# 8CH_Dimmer.net
KiCad netlist of a schematic drawn in EAGLE
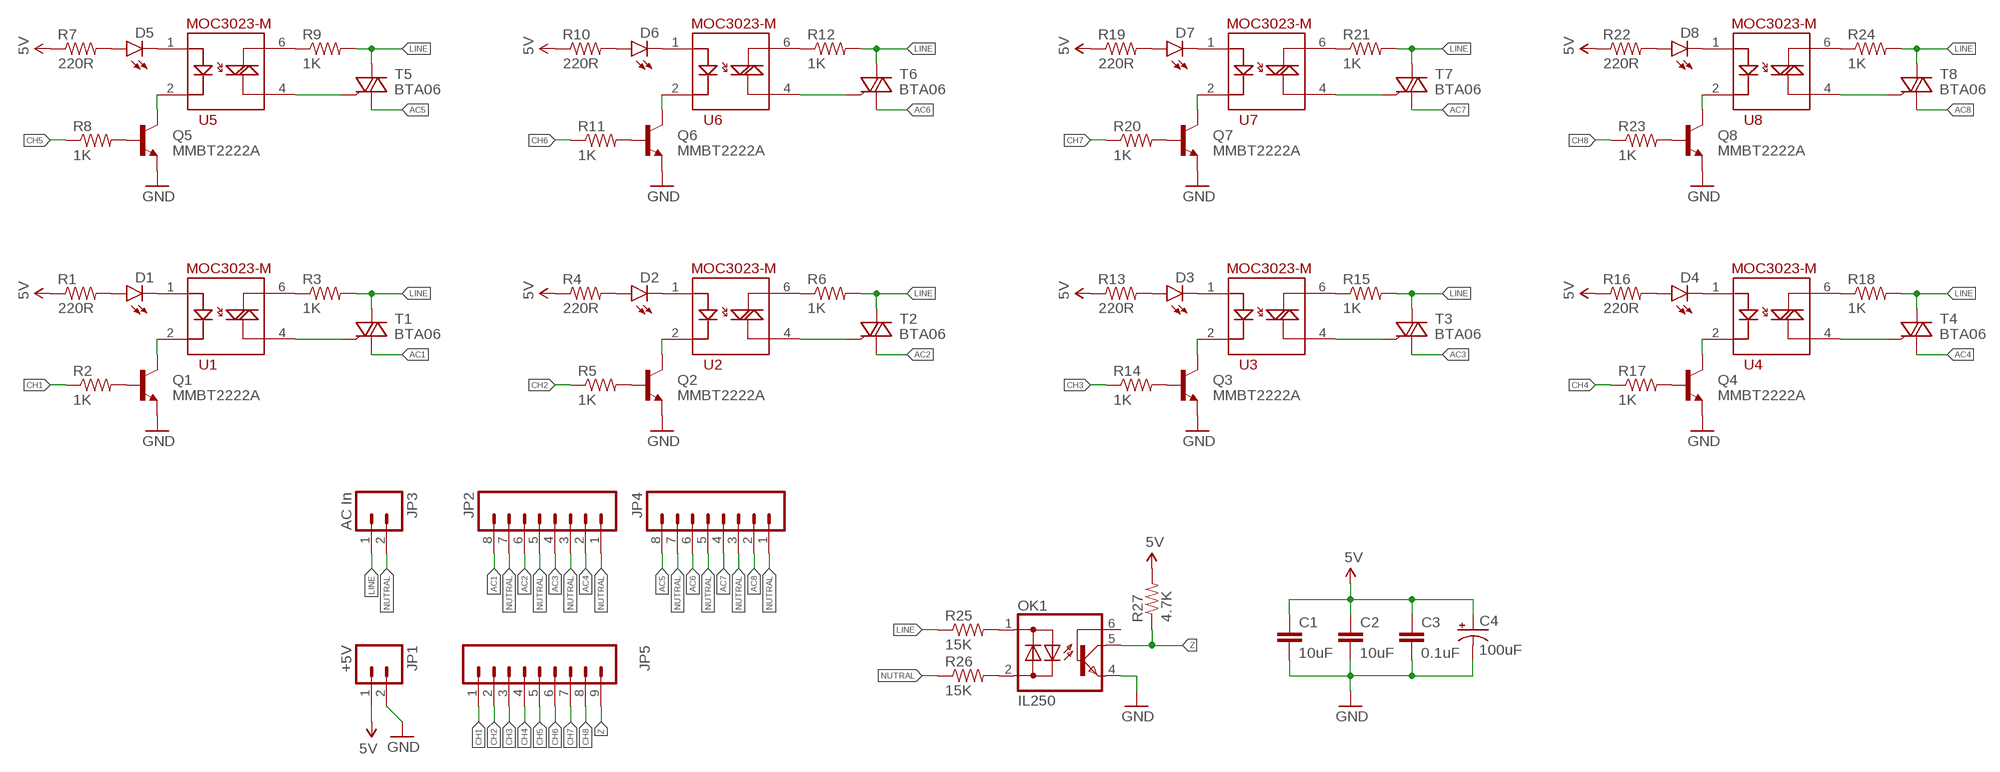
[diagram p0: schematic, sheet 1]

(export (version "E")
  (design (tool "Eeschema 10.0.6"))
  (components
    (comp (ref "C1")
      (value "10uF")
      (footprint "eagle-import:0805")
      (libsource (lib "eagle-import") (part "CAP0805"))
    )
    (comp (ref "C2")
      (value "10uF")
      (footprint "eagle-import:0805")
      (libsource (lib "eagle-import") (part "CAP0805"))
    )
    (comp (ref "C3")
      (value "0.1uF")
      (footprint "eagle-import:0805")
      (libsource (lib "eagle-import") (part "CAP0805"))
    )
    (comp (ref "C4")
      (value "100uF")
      (footprint "eagle-import:E2,5-5")
      (libsource (lib "eagle-import") (part "CPOL-USE2.5-5"))
    )
    (comp (ref "D1")
      (value "LED3MM")
      (footprint "eagle-import:LED3MM")
      (libsource (lib "eagle-import") (part "LED3MM"))
    )
    (comp (ref "D2")
      (value "LED3MM")
      (footprint "eagle-import:LED3MM")
      (libsource (lib "eagle-import") (part "LED3MM"))
    )
    (comp (ref "D3")
      (value "LED3MM")
      (footprint "eagle-import:LED3MM")
      (libsource (lib "eagle-import") (part "LED3MM"))
    )
    (comp (ref "D4")
      (value "LED3MM")
      (footprint "eagle-import:LED3MM")
      (libsource (lib "eagle-import") (part "LED3MM"))
    )
    (comp (ref "D5")
      (value "LED3MM")
      (footprint "eagle-import:LED3MM")
      (libsource (lib "eagle-import") (part "LED3MM"))
    )
    (comp (ref "D6")
      (value "LED3MM")
      (footprint "eagle-import:LED3MM")
      (libsource (lib "eagle-import") (part "LED3MM"))
    )
    (comp (ref "D7")
      (value "LED3MM")
      (footprint "eagle-import:LED3MM")
      (libsource (lib "eagle-import") (part "LED3MM"))
    )
    (comp (ref "D8")
      (value "LED3MM")
      (footprint "eagle-import:LED3MM")
      (libsource (lib "eagle-import") (part "LED3MM"))
    )
    (comp (ref "JP1")
      (value "+5V")
      (footprint "eagle-import:SCREWTERMINAL-3.5MM-2")
      (libsource (lib "eagle-import") (part "M023.5MM"))
    )
    (comp (ref "JP2")
      (value "M083.5MM-8")
      (footprint "eagle-import:SCREWTERMINAL-3.5MM-8")
      (libsource (lib "eagle-import") (part "M083.5MM-8"))
    )
    (comp (ref "JP3")
      (value "AC In")
      (footprint "eagle-import:SCREWTERMINAL-3.5MM-2")
      (libsource (lib "eagle-import") (part "M023.5MM"))
    )
    (comp (ref "JP4")
      (value "M083.5MM-8")
      (footprint "eagle-import:SCREWTERMINAL-3.5MM-8")
      (libsource (lib "eagle-import") (part "M083.5MM-8"))
    )
    (comp (ref "JP5")
      (value "M09")
      (footprint "eagle-import:1X09")
      (libsource (lib "eagle-import") (part "M09"))
    )
    (comp (ref "OK1")
      (value "IL250")
      (footprint "eagle-import:DIL06")
      (fields (field (name "MF") "VISHAY/TELEFUNKEN"))
      (libsource (lib "eagle-import") (part "IL250"))
    )
    (comp (ref "Q1")
      (value "MMBT2222A")
      (footprint "eagle-import:SOT23-3")
      (libsource (lib "eagle-import") (part "TRANSISTOR_NPNMMBT2222A"))
    )
    (comp (ref "Q2")
      (value "MMBT2222A")
      (footprint "eagle-import:SOT23-3")
      (libsource (lib "eagle-import") (part "TRANSISTOR_NPNMMBT2222A"))
    )
    (comp (ref "Q3")
      (value "MMBT2222A")
      (footprint "eagle-import:SOT23-3")
      (libsource (lib "eagle-import") (part "TRANSISTOR_NPNMMBT2222A"))
    )
    (comp (ref "Q4")
      (value "MMBT2222A")
      (footprint "eagle-import:SOT23-3")
      (libsource (lib "eagle-import") (part "TRANSISTOR_NPNMMBT2222A"))
    )
    (comp (ref "Q5")
      (value "MMBT2222A")
      (footprint "eagle-import:SOT23-3")
      (libsource (lib "eagle-import") (part "TRANSISTOR_NPNMMBT2222A"))
    )
    (comp (ref "Q6")
      (value "MMBT2222A")
      (footprint "eagle-import:SOT23-3")
      (libsource (lib "eagle-import") (part "TRANSISTOR_NPNMMBT2222A"))
    )
    (comp (ref "Q7")
      (value "MMBT2222A")
      (footprint "eagle-import:SOT23-3")
      (libsource (lib "eagle-import") (part "TRANSISTOR_NPNMMBT2222A"))
    )
    (comp (ref "Q8")
      (value "MMBT2222A")
      (footprint "eagle-import:SOT23-3")
      (libsource (lib "eagle-import") (part "TRANSISTOR_NPNMMBT2222A"))
    )
    (comp (ref "R1")
      (value "220R")
      (footprint "eagle-import:0805")
      (libsource (lib "eagle-import") (part "RESISTOR0805-RES"))
    )
    (comp (ref "R2")
      (value "1K")
      (footprint "eagle-import:0805")
      (libsource (lib "eagle-import") (part "RESISTOR0805-RES"))
    )
    (comp (ref "R3")
      (value "1K")
      (footprint "eagle-import:AXIAL-0.5")
      (libsource (lib "eagle-import") (part "RESISTORPTH-1/2W"))
    )
    (comp (ref "R4")
      (value "220R")
      (footprint "eagle-import:0805")
      (libsource (lib "eagle-import") (part "RESISTOR0805-RES"))
    )
    (comp (ref "R5")
      (value "1K")
      (footprint "eagle-import:0805")
      (libsource (lib "eagle-import") (part "RESISTOR0805-RES"))
    )
    (comp (ref "R6")
      (value "1K")
      (footprint "eagle-import:AXIAL-0.5")
      (libsource (lib "eagle-import") (part "RESISTORPTH-1/2W"))
    )
    (comp (ref "R7")
      (value "220R")
      (footprint "eagle-import:0805")
      (libsource (lib "eagle-import") (part "RESISTOR0805-RES"))
    )
    (comp (ref "R8")
      (value "1K")
      (footprint "eagle-import:0805")
      (libsource (lib "eagle-import") (part "RESISTOR0805-RES"))
    )
    (comp (ref "R9")
      (value "1K")
      (footprint "eagle-import:AXIAL-0.5")
      (libsource (lib "eagle-import") (part "RESISTORPTH-1/2W"))
    )
    (comp (ref "R10")
      (value "220R")
      (footprint "eagle-import:0805")
      (libsource (lib "eagle-import") (part "RESISTOR0805-RES"))
    )
    (comp (ref "R11")
      (value "1K")
      (footprint "eagle-import:0805")
      (libsource (lib "eagle-import") (part "RESISTOR0805-RES"))
    )
    (comp (ref "R12")
      (value "1K")
      (footprint "eagle-import:AXIAL-0.5")
      (libsource (lib "eagle-import") (part "RESISTORPTH-1/2W"))
    )
    (comp (ref "R13")
      (value "220R")
      (footprint "eagle-import:0805")
      (libsource (lib "eagle-import") (part "RESISTOR0805-RES"))
    )
    (comp (ref "R14")
      (value "1K")
      (footprint "eagle-import:0805")
      (libsource (lib "eagle-import") (part "RESISTOR0805-RES"))
    )
    (comp (ref "R15")
      (value "1K")
      (footprint "eagle-import:AXIAL-0.5")
      (libsource (lib "eagle-import") (part "RESISTORPTH-1/2W"))
    )
    (comp (ref "R16")
      (value "220R")
      (footprint "eagle-import:0805")
      (libsource (lib "eagle-import") (part "RESISTOR0805-RES"))
    )
    (comp (ref "R17")
      (value "1K")
      (footprint "eagle-import:0805")
      (libsource (lib "eagle-import") (part "RESISTOR0805-RES"))
    )
    (comp (ref "R18")
      (value "1K")
      (footprint "eagle-import:AXIAL-0.5")
      (libsource (lib "eagle-import") (part "RESISTORPTH-1/2W"))
    )
    (comp (ref "R19")
      (value "220R")
      (footprint "eagle-import:0805")
      (libsource (lib "eagle-import") (part "RESISTOR0805-RES"))
    )
    (comp (ref "R20")
      (value "1K")
      (footprint "eagle-import:0805")
      (libsource (lib "eagle-import") (part "RESISTOR0805-RES"))
    )
    (comp (ref "R21")
      (value "1K")
      (footprint "eagle-import:AXIAL-0.5")
      (libsource (lib "eagle-import") (part "RESISTORPTH-1/2W"))
    )
    (comp (ref "R22")
      (value "220R")
      (footprint "eagle-import:0805")
      (libsource (lib "eagle-import") (part "RESISTOR0805-RES"))
    )
    (comp (ref "R23")
      (value "1K")
      (footprint "eagle-import:0805")
      (libsource (lib "eagle-import") (part "RESISTOR0805-RES"))
    )
    (comp (ref "R24")
      (value "1K")
      (footprint "eagle-import:AXIAL-0.5")
      (libsource (lib "eagle-import") (part "RESISTORPTH-1/2W"))
    )
    (comp (ref "R25")
      (value "15K")
      (footprint "eagle-import:AXIAL-0.5")
      (libsource (lib "eagle-import") (part "RESISTORPTH-1/2W"))
    )
    (comp (ref "R26")
      (value "15K")
      (footprint "eagle-import:AXIAL-0.5")
      (libsource (lib "eagle-import") (part "RESISTORPTH-1/2W"))
    )
    (comp (ref "R27")
      (value "4.7K")
      (footprint "eagle-import:0805")
      (libsource (lib "eagle-import") (part "RESISTOR0805-RES"))
    )
    (comp (ref "T1")
      (value "BTA06")
      (footprint "eagle-import:TO220-V")
      (libsource (lib "eagle-import") (part "BTA06"))
    )
    (comp (ref "T2")
      (value "BTA06")
      (footprint "eagle-import:TO220-V")
      (libsource (lib "eagle-import") (part "BTA06"))
    )
    (comp (ref "T3")
      (value "BTA06")
      (footprint "eagle-import:TO220-V")
      (libsource (lib "eagle-import") (part "BTA06"))
    )
    (comp (ref "T4")
      (value "BTA06")
      (footprint "eagle-import:TO220-V")
      (libsource (lib "eagle-import") (part "BTA06"))
    )
    (comp (ref "T5")
      (value "BTA06")
      (footprint "eagle-import:TO220-V")
      (libsource (lib "eagle-import") (part "BTA06"))
    )
    (comp (ref "T6")
      (value "BTA06")
      (footprint "eagle-import:TO220-V")
      (libsource (lib "eagle-import") (part "BTA06"))
    )
    (comp (ref "T7")
      (value "BTA06")
      (footprint "eagle-import:TO220-V")
      (libsource (lib "eagle-import") (part "BTA06"))
    )
    (comp (ref "T8")
      (value "BTA06")
      (footprint "eagle-import:TO220-V")
      (libsource (lib "eagle-import") (part "BTA06"))
    )
    (comp (ref "U1")
      (value "MOC3023-M")
      (footprint "eagle-import:DIL06")
      (libsource (lib "eagle-import") (part "MOC3031-M"))
    )
    (comp (ref "U2")
      (value "MOC3023-M")
      (footprint "eagle-import:DIL06")
      (libsource (lib "eagle-import") (part "MOC3031-M"))
    )
    (comp (ref "U3")
      (value "MOC3023-M")
      (footprint "eagle-import:DIL06")
      (libsource (lib "eagle-import") (part "MOC3031-M"))
    )
    (comp (ref "U4")
      (value "MOC3023-M")
      (footprint "eagle-import:DIL06")
      (libsource (lib "eagle-import") (part "MOC3031-M"))
    )
    (comp (ref "U5")
      (value "MOC3023-M")
      (footprint "eagle-import:DIL06")
      (libsource (lib "eagle-import") (part "MOC3031-M"))
    )
    (comp (ref "U6")
      (value "MOC3023-M")
      (footprint "eagle-import:DIL06")
      (libsource (lib "eagle-import") (part "MOC3031-M"))
    )
    (comp (ref "U7")
      (value "MOC3023-M")
      (footprint "eagle-import:DIL06")
      (libsource (lib "eagle-import") (part "MOC3031-M"))
    )
    (comp (ref "U8")
      (value "MOC3023-M")
      (footprint "eagle-import:DIL06")
      (libsource (lib "eagle-import") (part "MOC3031-M"))
    )
  )
  (nets
    (net (code "1") (name "5V") (class "Default")
      (node (ref "C1") (pin "1") (pinfunction "1_1") (pintype "passive"))
      (node (ref "C2") (pin "1") (pinfunction "1_1") (pintype "passive"))
      (node (ref "C3") (pin "1") (pinfunction "1_1") (pintype "passive"))
      (node (ref "C4") (pin "+") (pinfunction "+_+") (pintype "passive"))
      (node (ref "JP1") (pin "1") (pinfunction "1_1") (pintype "passive"))
      (node (ref "R1") (pin "1") (pinfunction "1_1") (pintype "passive"))
      (node (ref "R10") (pin "1") (pinfunction "1_1") (pintype "passive"))
      (node (ref "R13") (pin "1") (pinfunction "1_1") (pintype "passive"))
      (node (ref "R16") (pin "1") (pinfunction "1_1") (pintype "passive"))
      (node (ref "R19") (pin "1") (pinfunction "1_1") (pintype "passive"))
      (node (ref "R22") (pin "1") (pinfunction "1_1") (pintype "passive"))
      (node (ref "R27") (pin "2") (pinfunction "2_2") (pintype "passive"))
      (node (ref "R4") (pin "1") (pinfunction "1_1") (pintype "passive"))
      (node (ref "R7") (pin "1") (pinfunction "1_1") (pintype "passive"))
    )
    (net (code "2") (name "AC1") (class "Default")
      (node (ref "JP2") (pin "8") (pinfunction "8_8") (pintype "passive"))
      (node (ref "T1") (pin "1") (pinfunction "A1_1") (pintype "passive"))
    )
    (net (code "3") (name "AC2") (class "Default")
      (node (ref "JP2") (pin "6") (pinfunction "6_6") (pintype "passive"))
      (node (ref "T2") (pin "1") (pinfunction "A1_1") (pintype "passive"))
    )
    (net (code "4") (name "AC3") (class "Default")
      (node (ref "JP2") (pin "4") (pinfunction "4_4") (pintype "passive"))
      (node (ref "T3") (pin "1") (pinfunction "A1_1") (pintype "passive"))
    )
    (net (code "5") (name "AC4") (class "Default")
      (node (ref "JP2") (pin "2") (pinfunction "2_2") (pintype "passive"))
      (node (ref "T4") (pin "1") (pinfunction "A1_1") (pintype "passive"))
    )
    (net (code "6") (name "AC5") (class "Default")
      (node (ref "JP4") (pin "8") (pinfunction "8_8") (pintype "passive"))
      (node (ref "T5") (pin "1") (pinfunction "A1_1") (pintype "passive"))
    )
    (net (code "7") (name "AC6") (class "Default")
      (node (ref "JP4") (pin "6") (pinfunction "6_6") (pintype "passive"))
      (node (ref "T6") (pin "1") (pinfunction "A1_1") (pintype "passive"))
    )
    (net (code "8") (name "AC7") (class "Default")
      (node (ref "JP4") (pin "4") (pinfunction "4_4") (pintype "passive"))
      (node (ref "T7") (pin "1") (pinfunction "A1_1") (pintype "passive"))
    )
    (net (code "9") (name "AC8") (class "Default")
      (node (ref "JP4") (pin "2") (pinfunction "2_2") (pintype "passive"))
      (node (ref "T8") (pin "1") (pinfunction "A1_1") (pintype "passive"))
    )
    (net (code "10") (name "CH1") (class "Default")
      (node (ref "JP5") (pin "1") (pinfunction "1_1") (pintype "passive"))
      (node (ref "R2") (pin "1") (pinfunction "1_1") (pintype "passive"))
    )
    (net (code "11") (name "CH2") (class "Default")
      (node (ref "JP5") (pin "2") (pinfunction "2_2") (pintype "passive"))
      (node (ref "R5") (pin "1") (pinfunction "1_1") (pintype "passive"))
    )
    (net (code "12") (name "CH3") (class "Default")
      (node (ref "JP5") (pin "3") (pinfunction "3_3") (pintype "passive"))
      (node (ref "R14") (pin "1") (pinfunction "1_1") (pintype "passive"))
    )
    (net (code "13") (name "CH4") (class "Default")
      (node (ref "JP5") (pin "4") (pinfunction "4_4") (pintype "passive"))
      (node (ref "R17") (pin "1") (pinfunction "1_1") (pintype "passive"))
    )
    (net (code "14") (name "CH5") (class "Default")
      (node (ref "JP5") (pin "5") (pinfunction "5_5") (pintype "passive"))
      (node (ref "R8") (pin "1") (pinfunction "1_1") (pintype "passive"))
    )
    (net (code "15") (name "CH6") (class "Default")
      (node (ref "JP5") (pin "6") (pinfunction "6_6") (pintype "passive"))
      (node (ref "R11") (pin "1") (pinfunction "1_1") (pintype "passive"))
    )
    (net (code "16") (name "CH7") (class "Default")
      (node (ref "JP5") (pin "7") (pinfunction "7_7") (pintype "passive"))
      (node (ref "R20") (pin "1") (pinfunction "1_1") (pintype "passive"))
    )
    (net (code "17") (name "CH8") (class "Default")
      (node (ref "JP5") (pin "8") (pinfunction "8_8") (pintype "passive"))
      (node (ref "R23") (pin "1") (pinfunction "1_1") (pintype "passive"))
    )
    (net (code "18") (name "GND") (class "Default")
      (node (ref "C1") (pin "2") (pinfunction "2_2") (pintype "passive"))
      (node (ref "C2") (pin "2") (pinfunction "2_2") (pintype "passive"))
      (node (ref "C3") (pin "2") (pinfunction "2_2") (pintype "passive"))
      (node (ref "C4") (pin "-") (pinfunction "-_-") (pintype "passive"))
      (node (ref "JP1") (pin "2") (pinfunction "2_2") (pintype "passive"))
      (node (ref "OK1") (pin "4") (pinfunction "E_4") (pintype "passive"))
      (node (ref "Q1") (pin "2") (pinfunction "E_2") (pintype "passive"))
      (node (ref "Q2") (pin "2") (pinfunction "E_2") (pintype "passive"))
      (node (ref "Q3") (pin "2") (pinfunction "E_2") (pintype "passive"))
      (node (ref "Q4") (pin "2") (pinfunction "E_2") (pintype "passive"))
      (node (ref "Q5") (pin "2") (pinfunction "E_2") (pintype "passive"))
      (node (ref "Q6") (pin "2") (pinfunction "E_2") (pintype "passive"))
      (node (ref "Q7") (pin "2") (pinfunction "E_2") (pintype "passive"))
      (node (ref "Q8") (pin "2") (pinfunction "E_2") (pintype "passive"))
    )
    (net (code "19") (name "LINE") (class "Default")
      (node (ref "JP3") (pin "1") (pinfunction "1_1") (pintype "passive"))
      (node (ref "R12") (pin "P$2") (pinfunction "2_P$2") (pintype "passive"))
      (node (ref "R15") (pin "P$2") (pinfunction "2_P$2") (pintype "passive"))
      (node (ref "R18") (pin "P$2") (pinfunction "2_P$2") (pintype "passive"))
      (node (ref "R21") (pin "P$2") (pinfunction "2_P$2") (pintype "passive"))
      (node (ref "R24") (pin "P$2") (pinfunction "2_P$2") (pintype "passive"))
      (node (ref "R25") (pin "P$1") (pinfunction "1_P$1") (pintype "passive"))
      (node (ref "R3") (pin "P$2") (pinfunction "2_P$2") (pintype "passive"))
      (node (ref "R6") (pin "P$2") (pinfunction "2_P$2") (pintype "passive"))
      (node (ref "R9") (pin "P$2") (pinfunction "2_P$2") (pintype "passive"))
      (node (ref "T1") (pin "2") (pinfunction "A2_2") (pintype "passive"))
      (node (ref "T2") (pin "2") (pinfunction "A2_2") (pintype "passive"))
      (node (ref "T3") (pin "2") (pinfunction "A2_2") (pintype "passive"))
      (node (ref "T4") (pin "2") (pinfunction "A2_2") (pintype "passive"))
      (node (ref "T5") (pin "2") (pinfunction "A2_2") (pintype "passive"))
      (node (ref "T6") (pin "2") (pinfunction "A2_2") (pintype "passive"))
      (node (ref "T7") (pin "2") (pinfunction "A2_2") (pintype "passive"))
      (node (ref "T8") (pin "2") (pinfunction "A2_2") (pintype "passive"))
    )
    (net (code "20") (name "NUTRAL") (class "Default")
      (node (ref "JP2") (pin "1") (pinfunction "1_1") (pintype "passive"))
      (node (ref "JP2") (pin "3") (pinfunction "3_3") (pintype "passive"))
      (node (ref "JP2") (pin "5") (pinfunction "5_5") (pintype "passive"))
      (node (ref "JP2") (pin "7") (pinfunction "7_7") (pintype "passive"))
      (node (ref "JP3") (pin "2") (pinfunction "2_2") (pintype "passive"))
      (node (ref "JP4") (pin "1") (pinfunction "1_1") (pintype "passive"))
      (node (ref "JP4") (pin "3") (pinfunction "3_3") (pintype "passive"))
      (node (ref "JP4") (pin "5") (pinfunction "5_5") (pintype "passive"))
      (node (ref "JP4") (pin "7") (pinfunction "7_7") (pintype "passive"))
      (node (ref "R26") (pin "P$1") (pinfunction "1_P$1") (pintype "passive"))
    )
    (net (code "21") (name "Net-(D1-C)") (class "Default")
      (node (ref "D1") (pin "K") (pinfunction "C_K") (pintype "passive"))
      (node (ref "U1") (pin "1") (pinfunction "1_1") (pintype "bidirectional"))
    )
    (net (code "22") (name "Net-(D1-PadA)") (class "Default")
      (node (ref "D1") (pin "A") (pinfunction "A_A") (pintype "passive"))
      (node (ref "R1") (pin "2") (pinfunction "2_2") (pintype "passive"))
    )
    (net (code "23") (name "Net-(D2-C)") (class "Default")
      (node (ref "D2") (pin "K") (pinfunction "C_K") (pintype "passive"))
      (node (ref "U2") (pin "1") (pinfunction "1_1") (pintype "bidirectional"))
    )
    (net (code "24") (name "Net-(D2-PadA)") (class "Default")
      (node (ref "D2") (pin "A") (pinfunction "A_A") (pintype "passive"))
      (node (ref "R4") (pin "2") (pinfunction "2_2") (pintype "passive"))
    )
    (net (code "25") (name "Net-(D3-C)") (class "Default")
      (node (ref "D3") (pin "K") (pinfunction "C_K") (pintype "passive"))
      (node (ref "U3") (pin "1") (pinfunction "1_1") (pintype "bidirectional"))
    )
    (net (code "26") (name "Net-(D3-PadA)") (class "Default")
      (node (ref "D3") (pin "A") (pinfunction "A_A") (pintype "passive"))
      (node (ref "R13") (pin "2") (pinfunction "2_2") (pintype "passive"))
    )
    (net (code "27") (name "Net-(D4-C)") (class "Default")
      (node (ref "D4") (pin "K") (pinfunction "C_K") (pintype "passive"))
      (node (ref "U4") (pin "1") (pinfunction "1_1") (pintype "bidirectional"))
    )
    (net (code "28") (name "Net-(D4-PadA)") (class "Default")
      (node (ref "D4") (pin "A") (pinfunction "A_A") (pintype "passive"))
      (node (ref "R16") (pin "2") (pinfunction "2_2") (pintype "passive"))
    )
    (net (code "29") (name "Net-(D5-C)") (class "Default")
      (node (ref "D5") (pin "K") (pinfunction "C_K") (pintype "passive"))
      (node (ref "U5") (pin "1") (pinfunction "1_1") (pintype "bidirectional"))
    )
    (net (code "30") (name "Net-(D5-PadA)") (class "Default")
      (node (ref "D5") (pin "A") (pinfunction "A_A") (pintype "passive"))
      (node (ref "R7") (pin "2") (pinfunction "2_2") (pintype "passive"))
    )
    (net (code "31") (name "Net-(D6-C)") (class "Default")
      (node (ref "D6") (pin "K") (pinfunction "C_K") (pintype "passive"))
      (node (ref "U6") (pin "1") (pinfunction "1_1") (pintype "bidirectional"))
    )
    (net (code "32") (name "Net-(D6-PadA)") (class "Default")
      (node (ref "D6") (pin "A") (pinfunction "A_A") (pintype "passive"))
      (node (ref "R10") (pin "2") (pinfunction "2_2") (pintype "passive"))
    )
    (net (code "33") (name "Net-(D7-C)") (class "Default")
      (node (ref "D7") (pin "K") (pinfunction "C_K") (pintype "passive"))
      (node (ref "U7") (pin "1") (pinfunction "1_1") (pintype "bidirectional"))
    )
    (net (code "34") (name "Net-(D7-PadA)") (class "Default")
      (node (ref "D7") (pin "A") (pinfunction "A_A") (pintype "passive"))
      (node (ref "R19") (pin "2") (pinfunction "2_2") (pintype "passive"))
    )
    (net (code "35") (name "Net-(D8-C)") (class "Default")
      (node (ref "D8") (pin "K") (pinfunction "C_K") (pintype "passive"))
      (node (ref "U8") (pin "1") (pinfunction "1_1") (pintype "bidirectional"))
    )
    (net (code "36") (name "Net-(D8-PadA)") (class "Default")
      (node (ref "D8") (pin "A") (pinfunction "A_A") (pintype "passive"))
      (node (ref "R22") (pin "2") (pinfunction "2_2") (pintype "passive"))
    )
    (net (code "37") (name "Net-(OK1-AC1)") (class "Default")
      (node (ref "OK1") (pin "1") (pinfunction "AC1_1") (pintype "passive"))
      (node (ref "R25") (pin "P$2") (pinfunction "2_P$2") (pintype "passive"))
    )
    (net (code "38") (name "Net-(OK1-AC2)") (class "Default")
      (node (ref "OK1") (pin "2") (pinfunction "AC2_2") (pintype "passive"))
      (node (ref "R26") (pin "P$2") (pinfunction "2_P$2") (pintype "passive"))
    )
    (net (code "39") (name "Net-(Q1-B)") (class "Default")
      (node (ref "Q1") (pin "1") (pinfunction "B_1") (pintype "passive"))
      (node (ref "R2") (pin "2") (pinfunction "2_2") (pintype "passive"))
    )
    (net (code "40") (name "Net-(Q1-C)") (class "Default")
      (node (ref "Q1") (pin "3") (pinfunction "C_3") (pintype "passive"))
      (node (ref "U1") (pin "2") (pinfunction "2_2") (pintype "bidirectional"))
    )
    (net (code "41") (name "Net-(Q2-B)") (class "Default")
      (node (ref "Q2") (pin "1") (pinfunction "B_1") (pintype "passive"))
      (node (ref "R5") (pin "2") (pinfunction "2_2") (pintype "passive"))
    )
    (net (code "42") (name "Net-(Q2-C)") (class "Default")
      (node (ref "Q2") (pin "3") (pinfunction "C_3") (pintype "passive"))
      (node (ref "U2") (pin "2") (pinfunction "2_2") (pintype "bidirectional"))
    )
    (net (code "43") (name "Net-(Q3-B)") (class "Default")
      (node (ref "Q3") (pin "1") (pinfunction "B_1") (pintype "passive"))
      (node (ref "R14") (pin "2") (pinfunction "2_2") (pintype "passive"))
    )
    (net (code "44") (name "Net-(Q3-C)") (class "Default")
      (node (ref "Q3") (pin "3") (pinfunction "C_3") (pintype "passive"))
      (node (ref "U3") (pin "2") (pinfunction "2_2") (pintype "bidirectional"))
    )
    (net (code "45") (name "Net-(Q4-B)") (class "Default")
      (node (ref "Q4") (pin "1") (pinfunction "B_1") (pintype "passive"))
      (node (ref "R17") (pin "2") (pinfunction "2_2") (pintype "passive"))
    )
    (net (code "46") (name "Net-(Q4-C)") (class "Default")
      (node (ref "Q4") (pin "3") (pinfunction "C_3") (pintype "passive"))
      (node (ref "U4") (pin "2") (pinfunction "2_2") (pintype "bidirectional"))
    )
    (net (code "47") (name "Net-(Q5-B)") (class "Default")
      (node (ref "Q5") (pin "1") (pinfunction "B_1") (pintype "passive"))
      (node (ref "R8") (pin "2") (pinfunction "2_2") (pintype "passive"))
    )
    (net (code "48") (name "Net-(Q5-C)") (class "Default")
      (node (ref "Q5") (pin "3") (pinfunction "C_3") (pintype "passive"))
      (node (ref "U5") (pin "2") (pinfunction "2_2") (pintype "bidirectional"))
    )
    (net (code "49") (name "Net-(Q6-B)") (class "Default")
      (node (ref "Q6") (pin "1") (pinfunction "B_1") (pintype "passive"))
      (node (ref "R11") (pin "2") (pinfunction "2_2") (pintype "passive"))
    )
    (net (code "50") (name "Net-(Q6-C)") (class "Default")
      (node (ref "Q6") (pin "3") (pinfunction "C_3") (pintype "passive"))
      (node (ref "U6") (pin "2") (pinfunction "2_2") (pintype "bidirectional"))
    )
    (net (code "51") (name "Net-(Q7-B)") (class "Default")
      (node (ref "Q7") (pin "1") (pinfunction "B_1") (pintype "passive"))
      (node (ref "R20") (pin "2") (pinfunction "2_2") (pintype "passive"))
    )
    (net (code "52") (name "Net-(Q7-C)") (class "Default")
      (node (ref "Q7") (pin "3") (pinfunction "C_3") (pintype "passive"))
      (node (ref "U7") (pin "2") (pinfunction "2_2") (pintype "bidirectional"))
    )
    (net (code "53") (name "Net-(Q8-B)") (class "Default")
      (node (ref "Q8") (pin "1") (pinfunction "B_1") (pintype "passive"))
      (node (ref "R23") (pin "2") (pinfunction "2_2") (pintype "passive"))
    )
    (net (code "54") (name "Net-(Q8-C)") (class "Default")
      (node (ref "Q8") (pin "3") (pinfunction "C_3") (pintype "passive"))
      (node (ref "U8") (pin "2") (pinfunction "2_2") (pintype "bidirectional"))
    )
    (net (code "55") (name "Net-(R3-1)") (class "Default")
      (node (ref "R3") (pin "P$1") (pinfunction "1_P$1") (pintype "passive"))
      (node (ref "U1") (pin "6") (pinfunction "6_6") (pintype "bidirectional"))
    )
    (net (code "56") (name "Net-(R6-1)") (class "Default")
      (node (ref "R6") (pin "P$1") (pinfunction "1_P$1") (pintype "passive"))
      (node (ref "U2") (pin "6") (pinfunction "6_6") (pintype "bidirectional"))
    )
    (net (code "57") (name "Net-(R9-1)") (class "Default")
      (node (ref "R9") (pin "P$1") (pinfunction "1_P$1") (pintype "passive"))
      (node (ref "U5") (pin "6") (pinfunction "6_6") (pintype "bidirectional"))
    )
    (net (code "58") (name "Net-(R12-1)") (class "Default")
      (node (ref "R12") (pin "P$1") (pinfunction "1_P$1") (pintype "passive"))
      (node (ref "U6") (pin "6") (pinfunction "6_6") (pintype "bidirectional"))
    )
    (net (code "59") (name "Net-(R15-1)") (class "Default")
      (node (ref "R15") (pin "P$1") (pinfunction "1_P$1") (pintype "passive"))
      (node (ref "U3") (pin "6") (pinfunction "6_6") (pintype "bidirectional"))
    )
    (net (code "60") (name "Net-(R18-1)") (class "Default")
      (node (ref "R18") (pin "P$1") (pinfunction "1_P$1") (pintype "passive"))
      (node (ref "U4") (pin "6") (pinfunction "6_6") (pintype "bidirectional"))
    )
    (net (code "61") (name "Net-(R21-1)") (class "Default")
      (node (ref "R21") (pin "P$1") (pinfunction "1_P$1") (pintype "passive"))
      (node (ref "U7") (pin "6") (pinfunction "6_6") (pintype "bidirectional"))
    )
    (net (code "62") (name "Net-(R24-1)") (class "Default")
      (node (ref "R24") (pin "P$1") (pinfunction "1_P$1") (pintype "passive"))
      (node (ref "U8") (pin "6") (pinfunction "6_6") (pintype "bidirectional"))
    )
    (net (code "63") (name "Net-(T1-G)") (class "Default")
      (node (ref "T1") (pin "3") (pinfunction "G_3") (pintype "passive"))
      (node (ref "U1") (pin "4") (pinfunction "4_4") (pintype "bidirectional"))
    )
    (net (code "64") (name "Net-(T2-G)") (class "Default")
      (node (ref "T2") (pin "3") (pinfunction "G_3") (pintype "passive"))
      (node (ref "U2") (pin "4") (pinfunction "4_4") (pintype "bidirectional"))
    )
    (net (code "65") (name "Net-(T3-G)") (class "Default")
      (node (ref "T3") (pin "3") (pinfunction "G_3") (pintype "passive"))
      (node (ref "U3") (pin "4") (pinfunction "4_4") (pintype "bidirectional"))
    )
    (net (code "66") (name "Net-(T4-G)") (class "Default")
      (node (ref "T4") (pin "3") (pinfunction "G_3") (pintype "passive"))
      (node (ref "U4") (pin "4") (pinfunction "4_4") (pintype "bidirectional"))
    )
    (net (code "67") (name "Net-(T5-G)") (class "Default")
      (node (ref "T5") (pin "3") (pinfunction "G_3") (pintype "passive"))
      (node (ref "U5") (pin "4") (pinfunction "4_4") (pintype "bidirectional"))
    )
    (net (code "68") (name "Net-(T6-G)") (class "Default")
      (node (ref "T6") (pin "3") (pinfunction "G_3") (pintype "passive"))
      (node (ref "U6") (pin "4") (pinfunction "4_4") (pintype "bidirectional"))
    )
    (net (code "69") (name "Net-(T7-G)") (class "Default")
      (node (ref "T7") (pin "3") (pinfunction "G_3") (pintype "passive"))
      (node (ref "U7") (pin "4") (pinfunction "4_4") (pintype "bidirectional"))
    )
    (net (code "70") (name "Net-(T8-G)") (class "Default")
      (node (ref "T8") (pin "3") (pinfunction "G_3") (pintype "passive"))
      (node (ref "U8") (pin "4") (pinfunction "4_4") (pintype "bidirectional"))
    )
    (net (code "71") (name "Z") (class "Default")
      (node (ref "JP5") (pin "9") (pinfunction "9_9") (pintype "passive"))
      (node (ref "OK1") (pin "5") (pinfunction "C_5") (pintype "passive"))
      (node (ref "R27") (pin "1") (pinfunction "1_1") (pintype "passive"))
    )
    (net (code "72") (name "unconnected-(OK1-B-Pad6)") (class "Default")
      (node (ref "OK1") (pin "6") (pinfunction "B_6") (pintype "passive"))
    )
  )
)
